# v3.net
KiCad netlist of a schematic drawn in EAGLE
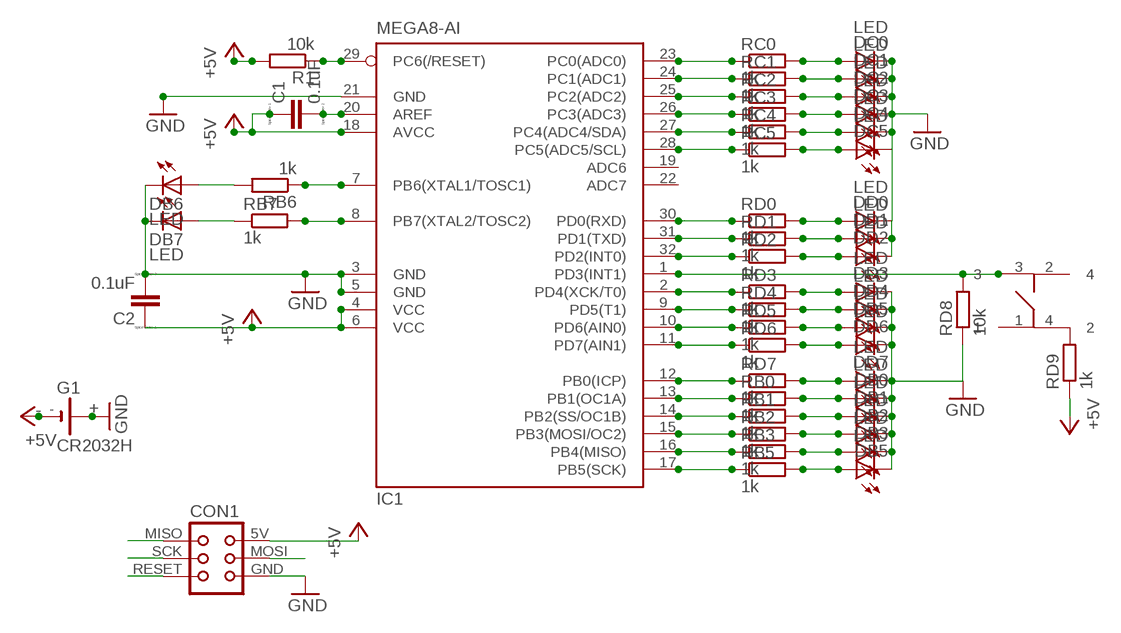
[diagram p0: schematic, sheet 1]

(export (version "E")
  (design (tool "Eeschema 10.0.6"))
  (components
    (comp (ref "C1")
      (value "0.1uF")
      (footprint "eagle-import:C0402")
      (libsource (lib "eagle-import") (part "CC0402"))
    )
    (comp (ref "C2")
      (value "0.1uF")
      (footprint "eagle-import:C0402")
      (libsource (lib "eagle-import") (part "CC0402"))
    )
    (comp (ref "CON1")
      (value "TINYISPT")
      (footprint "eagle-import:TC2030-MCP-NL")
      (libsource (lib "eagle-import") (part "TINYISPT"))
    )
    (comp (ref "DB0")
      (value "LED")
      (footprint "eagle-import:D0402")
      (libsource (lib "eagle-import") (part "LED"))
    )
    (comp (ref "DB1")
      (value "LED")
      (footprint "eagle-import:D0402")
      (libsource (lib "eagle-import") (part "LED"))
    )
    (comp (ref "DB2")
      (value "LED")
      (footprint "eagle-import:D0402")
      (libsource (lib "eagle-import") (part "LED"))
    )
    (comp (ref "DB3")
      (value "LED")
      (footprint "eagle-import:D0402")
      (libsource (lib "eagle-import") (part "LED"))
    )
    (comp (ref "DB5")
      (value "LED")
      (footprint "eagle-import:D0402")
      (libsource (lib "eagle-import") (part "LED"))
    )
    (comp (ref "DB6")
      (value "LED")
      (footprint "eagle-import:D0402")
      (libsource (lib "eagle-import") (part "LED"))
    )
    (comp (ref "DB7")
      (value "LED")
      (footprint "eagle-import:D0402")
      (libsource (lib "eagle-import") (part "LED"))
    )
    (comp (ref "DC0")
      (value "LED")
      (footprint "eagle-import:D0402")
      (libsource (lib "eagle-import") (part "LED"))
    )
    (comp (ref "DC1")
      (value "LED")
      (footprint "eagle-import:D0402")
      (libsource (lib "eagle-import") (part "LED"))
    )
    (comp (ref "DC2")
      (value "LED")
      (footprint "eagle-import:D0402")
      (libsource (lib "eagle-import") (part "LED"))
    )
    (comp (ref "DC3")
      (value "LED")
      (footprint "eagle-import:D0402")
      (libsource (lib "eagle-import") (part "LED"))
    )
    (comp (ref "DC4")
      (value "LED")
      (footprint "eagle-import:D0402")
      (libsource (lib "eagle-import") (part "LED"))
    )
    (comp (ref "DC5")
      (value "LED")
      (footprint "eagle-import:D0402")
      (libsource (lib "eagle-import") (part "LED"))
    )
    (comp (ref "DD0")
      (value "LED")
      (footprint "eagle-import:D0402")
      (libsource (lib "eagle-import") (part "LED"))
    )
    (comp (ref "DD1")
      (value "LED")
      (footprint "eagle-import:D0402")
      (libsource (lib "eagle-import") (part "LED"))
    )
    (comp (ref "DD2")
      (value "LED")
      (footprint "eagle-import:D0402")
      (libsource (lib "eagle-import") (part "LED"))
    )
    (comp (ref "DD3")
      (value "LED")
      (footprint "eagle-import:D0402")
      (libsource (lib "eagle-import") (part "LED"))
    )
    (comp (ref "DD4")
      (value "LED")
      (footprint "eagle-import:D0402")
      (libsource (lib "eagle-import") (part "LED"))
    )
    (comp (ref "DD5")
      (value "LED")
      (footprint "eagle-import:D0402")
      (libsource (lib "eagle-import") (part "LED"))
    )
    (comp (ref "DD6")
      (value "LED")
      (footprint "eagle-import:D0402")
      (libsource (lib "eagle-import") (part "LED"))
    )
    (comp (ref "DD7")
      (value "LED")
      (footprint "eagle-import:D0402")
      (libsource (lib "eagle-import") (part "LED"))
    )
    (comp (ref "G1")
      (value "CR2032H")
      (footprint "eagle-import:CR2032H")
      (libsource (lib "eagle-import") (part "CR2032H"))
    )
    (comp (ref "IC1")
      (value "MEGA8-AI")
      (footprint "eagle-import:TQFP32-08")
      (fields (field (name "MPN") "ATMEGA8-16AU"))
      (libsource (lib "eagle-import") (part "MEGA8-AI"))
    )
    (comp (ref "R1")
      (value "10k")
      (footprint "eagle-import:R0402")
      (libsource (lib "eagle-import") (part "R-EU_R0402"))
    )
    (comp (ref "RB0")
      (value "1k")
      (footprint "eagle-import:R0402")
      (libsource (lib "eagle-import") (part "R-EU_R0402"))
    )
    (comp (ref "RB1")
      (value "1k")
      (footprint "eagle-import:R0402")
      (libsource (lib "eagle-import") (part "R-EU_R0402"))
    )
    (comp (ref "RB2")
      (value "1k")
      (footprint "eagle-import:R0402")
      (libsource (lib "eagle-import") (part "R-EU_R0402"))
    )
    (comp (ref "RB3")
      (value "1k")
      (footprint "eagle-import:R0402")
      (libsource (lib "eagle-import") (part "R-EU_R0402"))
    )
    (comp (ref "RB5")
      (value "1k")
      (footprint "eagle-import:R0402")
      (libsource (lib "eagle-import") (part "R-EU_R0402"))
    )
    (comp (ref "RB6")
      (value "1k")
      (footprint "eagle-import:R0402")
      (libsource (lib "eagle-import") (part "R-EU_R0402"))
    )
    (comp (ref "RB7")
      (value "1k")
      (footprint "eagle-import:R0402")
      (libsource (lib "eagle-import") (part "R-EU_R0402"))
    )
    (comp (ref "RC0")
      (value "1k")
      (footprint "eagle-import:R0402")
      (libsource (lib "eagle-import") (part "R-EU_R0402"))
    )
    (comp (ref "RC1")
      (value "1k")
      (footprint "eagle-import:R0402")
      (libsource (lib "eagle-import") (part "R-EU_R0402"))
    )
    (comp (ref "RC2")
      (value "1k")
      (footprint "eagle-import:R0402")
      (libsource (lib "eagle-import") (part "R-EU_R0402"))
    )
    (comp (ref "RC3")
      (value "1k")
      (footprint "eagle-import:R0402")
      (libsource (lib "eagle-import") (part "R-EU_R0402"))
    )
    (comp (ref "RC4")
      (value "1k")
      (footprint "eagle-import:R0402")
      (libsource (lib "eagle-import") (part "R-EU_R0402"))
    )
    (comp (ref "RC5")
      (value "1k")
      (footprint "eagle-import:R0402")
      (libsource (lib "eagle-import") (part "R-EU_R0402"))
    )
    (comp (ref "RD0")
      (value "1k")
      (footprint "eagle-import:R0402")
      (libsource (lib "eagle-import") (part "R-EU_R0402"))
    )
    (comp (ref "RD1")
      (value "1k")
      (footprint "eagle-import:R0402")
      (libsource (lib "eagle-import") (part "R-EU_R0402"))
    )
    (comp (ref "RD2")
      (value "1k")
      (footprint "eagle-import:R0402")
      (libsource (lib "eagle-import") (part "R-EU_R0402"))
    )
    (comp (ref "RD3")
      (value "1k")
      (footprint "eagle-import:R0402")
      (libsource (lib "eagle-import") (part "R-EU_R0402"))
    )
    (comp (ref "RD4")
      (value "1k")
      (footprint "eagle-import:R0402")
      (libsource (lib "eagle-import") (part "R-EU_R0402"))
    )
    (comp (ref "RD5")
      (value "1k")
      (footprint "eagle-import:R0402")
      (libsource (lib "eagle-import") (part "R-EU_R0402"))
    )
    (comp (ref "RD6")
      (value "1k")
      (footprint "eagle-import:R0402")
      (libsource (lib "eagle-import") (part "R-EU_R0402"))
    )
    (comp (ref "RD7")
      (value "1k")
      (footprint "eagle-import:R0402")
      (libsource (lib "eagle-import") (part "R-EU_R0402"))
    )
    (comp (ref "RD8")
      (value "10k")
      (footprint "eagle-import:R0402")
      (libsource (lib "eagle-import") (part "R-EU_R0402"))
    )
    (comp (ref "RD9")
      (value "1k")
      (footprint "eagle-import:R0402")
      (libsource (lib "eagle-import") (part "R-EU_R0402"))
    )
    (comp (ref "U$2")
      (value "TEUCH4MM")
      (footprint "eagle-import:TEUCH4MM")
      (libsource (lib "eagle-import") (part "TEUCH4MM"))
    )
  )
  (nets
    (net (code "1") (name "+5V") (class "Default")
      (node (ref "C1") (pin "1") (pinfunction "1_1") (pintype "passive"))
      (node (ref "C2") (pin "1") (pinfunction "1_1") (pintype "passive"))
      (node (ref "CON1") (pin "5V") (pinfunction "VCC_5V") (pintype "passive"))
      (node (ref "G1") (pin "-") (pinfunction "-_-") (pintype "passive"))
      (node (ref "IC1") (pin "18") (pinfunction "AVCC_18") (pintype "power_in"))
      (node (ref "IC1") (pin "4") (pinfunction "VCC_4") (pintype "power_in"))
      (node (ref "IC1") (pin "6") (pinfunction "VCC_6") (pintype "power_in"))
      (node (ref "R1") (pin "2") (pinfunction "2_2") (pintype "passive"))
      (node (ref "RD9") (pin "1") (pinfunction "1_1") (pintype "passive"))
    )
    (net (code "2") (name "/RESET") (class "Default")
      (node (ref "CON1") (pin "RESET") (pinfunction "RESET_RESET") (pintype "passive"))
      (node (ref "IC1") (pin "29") (pinfunction "PC6(/RESET)_29") (pintype "bidirectional"))
      (node (ref "R1") (pin "1") (pinfunction "1_1") (pintype "passive"))
    )
    (net (code "3") (name "GND") (class "Default")
      (node (ref "C2") (pin "2") (pinfunction "2_2") (pintype "passive"))
      (node (ref "CON1") (pin "GND") (pinfunction "GND_GND") (pintype "passive"))
      (node (ref "DB0") (pin "C") (pinfunction "C_C") (pintype "passive"))
      (node (ref "DB1") (pin "C") (pinfunction "C_C") (pintype "passive"))
      (node (ref "DB2") (pin "C") (pinfunction "C_C") (pintype "passive"))
      (node (ref "DB3") (pin "C") (pinfunction "C_C") (pintype "passive"))
      (node (ref "DB5") (pin "C") (pinfunction "C_C") (pintype "passive"))
      (node (ref "DB6") (pin "C") (pinfunction "C_C") (pintype "passive"))
      (node (ref "DB7") (pin "C") (pinfunction "C_C") (pintype "passive"))
      (node (ref "DC0") (pin "C") (pinfunction "C_C") (pintype "passive"))
      (node (ref "DC1") (pin "C") (pinfunction "C_C") (pintype "passive"))
      (node (ref "DC2") (pin "C") (pinfunction "C_C") (pintype "passive"))
      (node (ref "DC3") (pin "C") (pinfunction "C_C") (pintype "passive"))
      (node (ref "DC4") (pin "C") (pinfunction "C_C") (pintype "passive"))
      (node (ref "DC5") (pin "C") (pinfunction "C_C") (pintype "passive"))
      (node (ref "DD0") (pin "C") (pinfunction "C_C") (pintype "passive"))
      (node (ref "DD1") (pin "C") (pinfunction "C_C") (pintype "passive"))
      (node (ref "DD2") (pin "C") (pinfunction "C_C") (pintype "passive"))
      (node (ref "DD3") (pin "C") (pinfunction "C_C") (pintype "passive"))
      (node (ref "DD4") (pin "C") (pinfunction "C_C") (pintype "passive"))
      (node (ref "DD5") (pin "C") (pinfunction "C_C") (pintype "passive"))
      (node (ref "DD6") (pin "C") (pinfunction "C_C") (pintype "passive"))
      (node (ref "DD7") (pin "C") (pinfunction "C_C") (pintype "passive"))
      (node (ref "G1") (pin "+") (pinfunction "+_+") (pintype "passive"))
      (node (ref "IC1") (pin "21") (pinfunction "GND_21") (pintype "power_in"))
      (node (ref "IC1") (pin "3") (pinfunction "GND_3") (pintype "power_in"))
      (node (ref "IC1") (pin "5") (pinfunction "GND_5") (pintype "power_in"))
      (node (ref "RD8") (pin "1") (pinfunction "1_1") (pintype "passive"))
    )
    (net (code "4") (name "Net-(DB0-PadA)") (class "Default")
      (node (ref "DB0") (pin "A") (pinfunction "A_A") (pintype "passive"))
      (node (ref "RB0") (pin "2") (pinfunction "2_2") (pintype "passive"))
    )
    (net (code "5") (name "Net-(DB1-PadA)") (class "Default")
      (node (ref "DB1") (pin "A") (pinfunction "A_A") (pintype "passive"))
      (node (ref "RB1") (pin "2") (pinfunction "2_2") (pintype "passive"))
    )
    (net (code "6") (name "Net-(DB2-PadA)") (class "Default")
      (node (ref "DB2") (pin "A") (pinfunction "A_A") (pintype "passive"))
      (node (ref "RB2") (pin "2") (pinfunction "2_2") (pintype "passive"))
    )
    (net (code "7") (name "Net-(DB3-PadA)") (class "Default")
      (node (ref "DB3") (pin "A") (pinfunction "A_A") (pintype "passive"))
      (node (ref "RB3") (pin "2") (pinfunction "2_2") (pintype "passive"))
    )
    (net (code "8") (name "Net-(DB5-PadA)") (class "Default")
      (node (ref "DB5") (pin "A") (pinfunction "A_A") (pintype "passive"))
      (node (ref "RB5") (pin "2") (pinfunction "2_2") (pintype "passive"))
    )
    (net (code "9") (name "Net-(DB6-PadA)") (class "Default")
      (node (ref "DB6") (pin "A") (pinfunction "A_A") (pintype "passive"))
      (node (ref "RB6") (pin "2") (pinfunction "2_2") (pintype "passive"))
    )
    (net (code "10") (name "Net-(DB7-PadA)") (class "Default")
      (node (ref "DB7") (pin "A") (pinfunction "A_A") (pintype "passive"))
      (node (ref "RB7") (pin "1") (pinfunction "1_1") (pintype "passive"))
    )
    (net (code "11") (name "Net-(DC0-PadA)") (class "Default")
      (node (ref "DC0") (pin "A") (pinfunction "A_A") (pintype "passive"))
      (node (ref "RC0") (pin "2") (pinfunction "2_2") (pintype "passive"))
    )
    (net (code "12") (name "Net-(DC1-PadA)") (class "Default")
      (node (ref "DC1") (pin "A") (pinfunction "A_A") (pintype "passive"))
      (node (ref "RC1") (pin "2") (pinfunction "2_2") (pintype "passive"))
    )
    (net (code "13") (name "Net-(DC2-PadA)") (class "Default")
      (node (ref "DC2") (pin "A") (pinfunction "A_A") (pintype "passive"))
      (node (ref "RC2") (pin "2") (pinfunction "2_2") (pintype "passive"))
    )
    (net (code "14") (name "Net-(DC3-PadA)") (class "Default")
      (node (ref "DC3") (pin "A") (pinfunction "A_A") (pintype "passive"))
      (node (ref "RC3") (pin "2") (pinfunction "2_2") (pintype "passive"))
    )
    (net (code "15") (name "Net-(DC4-PadA)") (class "Default")
      (node (ref "DC4") (pin "A") (pinfunction "A_A") (pintype "passive"))
      (node (ref "RC4") (pin "2") (pinfunction "2_2") (pintype "passive"))
    )
    (net (code "16") (name "Net-(DC5-PadA)") (class "Default")
      (node (ref "DC5") (pin "A") (pinfunction "A_A") (pintype "passive"))
      (node (ref "RC5") (pin "2") (pinfunction "2_2") (pintype "passive"))
    )
    (net (code "17") (name "Net-(DD0-PadA)") (class "Default")
      (node (ref "DD0") (pin "A") (pinfunction "A_A") (pintype "passive"))
      (node (ref "RD0") (pin "2") (pinfunction "2_2") (pintype "passive"))
    )
    (net (code "18") (name "Net-(DD1-PadA)") (class "Default")
      (node (ref "DD1") (pin "A") (pinfunction "A_A") (pintype "passive"))
      (node (ref "RD1") (pin "2") (pinfunction "2_2") (pintype "passive"))
    )
    (net (code "19") (name "Net-(DD2-PadA)") (class "Default")
      (node (ref "DD2") (pin "A") (pinfunction "A_A") (pintype "passive"))
      (node (ref "RD2") (pin "2") (pinfunction "2_2") (pintype "passive"))
    )
    (net (code "20") (name "Net-(DD3-PadA)") (class "Default")
      (node (ref "DD3") (pin "A") (pinfunction "A_A") (pintype "passive"))
      (node (ref "RD3") (pin "2") (pinfunction "2_2") (pintype "passive"))
    )
    (net (code "21") (name "Net-(DD4-PadA)") (class "Default")
      (node (ref "DD4") (pin "A") (pinfunction "A_A") (pintype "passive"))
      (node (ref "RD4") (pin "2") (pinfunction "2_2") (pintype "passive"))
    )
    (net (code "22") (name "Net-(DD5-PadA)") (class "Default")
      (node (ref "DD5") (pin "A") (pinfunction "A_A") (pintype "passive"))
      (node (ref "RD5") (pin "2") (pinfunction "2_2") (pintype "passive"))
    )
    (net (code "23") (name "Net-(DD6-PadA)") (class "Default")
      (node (ref "DD6") (pin "A") (pinfunction "A_A") (pintype "passive"))
      (node (ref "RD6") (pin "2") (pinfunction "2_2") (pintype "passive"))
    )
    (net (code "24") (name "Net-(DD7-PadA)") (class "Default")
      (node (ref "DD7") (pin "A") (pinfunction "A_A") (pintype "passive"))
      (node (ref "RD7") (pin "2") (pinfunction "2_2") (pintype "passive"))
    )
    (net (code "25") (name "Net-(IC1-AREF)") (class "Default")
      (node (ref "C1") (pin "2") (pinfunction "2_2") (pintype "passive"))
      (node (ref "IC1") (pin "20") (pinfunction "AREF_20") (pintype "passive"))
    )
    (net (code "26") (name "Net-(IC1-PB0(ICP))") (class "Default")
      (node (ref "IC1") (pin "12") (pinfunction "PB0(ICP)_12") (pintype "bidirectional"))
      (node (ref "RD7") (pin "1") (pinfunction "1_1") (pintype "passive"))
    )
    (net (code "27") (name "Net-(IC1-PB1(OC1A))") (class "Default")
      (node (ref "IC1") (pin "13") (pinfunction "PB1(OC1A)_13") (pintype "bidirectional"))
      (node (ref "RB0") (pin "1") (pinfunction "1_1") (pintype "passive"))
    )
    (net (code "28") (name "Net-(IC1-PB2(SS{slash}OC1B))") (class "Default")
      (node (ref "IC1") (pin "14") (pinfunction "PB2(SS/OC1B)_14") (pintype "bidirectional"))
      (node (ref "RB1") (pin "1") (pinfunction "1_1") (pintype "passive"))
    )
    (net (code "29") (name "Net-(IC1-PB3(MOSI{slash}OC2))") (class "Default")
      (node (ref "IC1") (pin "15") (pinfunction "PB3(MOSI/OC2)_15") (pintype "bidirectional"))
      (node (ref "RB2") (pin "1") (pinfunction "1_1") (pintype "passive"))
    )
    (net (code "30") (name "Net-(IC1-PB4(MISO))") (class "Default")
      (node (ref "IC1") (pin "16") (pinfunction "PB4(MISO)_16") (pintype "bidirectional"))
      (node (ref "RB3") (pin "1") (pinfunction "1_1") (pintype "passive"))
    )
    (net (code "31") (name "Net-(IC1-PB5(SCK))") (class "Default")
      (node (ref "IC1") (pin "17") (pinfunction "PB5(SCK)_17") (pintype "bidirectional"))
      (node (ref "RB5") (pin "1") (pinfunction "1_1") (pintype "passive"))
    )
    (net (code "32") (name "Net-(IC1-PB6(XTAL1{slash}TOSC1))") (class "Default")
      (node (ref "IC1") (pin "7") (pinfunction "PB6(XTAL1/TOSC1)_7") (pintype "bidirectional"))
      (node (ref "RB6") (pin "1") (pinfunction "1_1") (pintype "passive"))
    )
    (net (code "33") (name "Net-(IC1-PB7(XTAL2{slash}TOSC2))") (class "Default")
      (node (ref "IC1") (pin "8") (pinfunction "PB7(XTAL2/TOSC2)_8") (pintype "bidirectional"))
      (node (ref "RB7") (pin "2") (pinfunction "2_2") (pintype "passive"))
    )
    (net (code "34") (name "Net-(IC1-PC0(ADC0))") (class "Default")
      (node (ref "IC1") (pin "23") (pinfunction "PC0(ADC0)_23") (pintype "bidirectional"))
      (node (ref "RC0") (pin "1") (pinfunction "1_1") (pintype "passive"))
    )
    (net (code "35") (name "Net-(IC1-PC1(ADC1))") (class "Default")
      (node (ref "IC1") (pin "24") (pinfunction "PC1(ADC1)_24") (pintype "bidirectional"))
      (node (ref "RC1") (pin "1") (pinfunction "1_1") (pintype "passive"))
    )
    (net (code "36") (name "Net-(IC1-PC2(ADC2))") (class "Default")
      (node (ref "IC1") (pin "25") (pinfunction "PC2(ADC2)_25") (pintype "bidirectional"))
      (node (ref "RC2") (pin "1") (pinfunction "1_1") (pintype "passive"))
    )
    (net (code "37") (name "Net-(IC1-PC3(ADC3))") (class "Default")
      (node (ref "IC1") (pin "26") (pinfunction "PC3(ADC3)_26") (pintype "bidirectional"))
      (node (ref "RC3") (pin "1") (pinfunction "1_1") (pintype "passive"))
    )
    (net (code "38") (name "Net-(IC1-PC4(ADC4{slash}SDA))") (class "Default")
      (node (ref "IC1") (pin "27") (pinfunction "PC4(ADC4/SDA)_27") (pintype "bidirectional"))
      (node (ref "RC4") (pin "1") (pinfunction "1_1") (pintype "passive"))
    )
    (net (code "39") (name "Net-(IC1-PC5(ADC5{slash}SCL))") (class "Default")
      (node (ref "IC1") (pin "28") (pinfunction "PC5(ADC5/SCL)_28") (pintype "bidirectional"))
      (node (ref "RC5") (pin "1") (pinfunction "1_1") (pintype "passive"))
    )
    (net (code "40") (name "Net-(IC1-PD0(RXD))") (class "Default")
      (node (ref "IC1") (pin "30") (pinfunction "PD0(RXD)_30") (pintype "bidirectional"))
      (node (ref "RD0") (pin "1") (pinfunction "1_1") (pintype "passive"))
    )
    (net (code "41") (name "Net-(IC1-PD1(TXD))") (class "Default")
      (node (ref "IC1") (pin "31") (pinfunction "PD1(TXD)_31") (pintype "bidirectional"))
      (node (ref "RD1") (pin "1") (pinfunction "1_1") (pintype "passive"))
    )
    (net (code "42") (name "Net-(IC1-PD2(INT0))") (class "Default")
      (node (ref "IC1") (pin "32") (pinfunction "PD2(INT0)_32") (pintype "bidirectional"))
      (node (ref "RD2") (pin "1") (pinfunction "1_1") (pintype "passive"))
    )
    (net (code "43") (name "Net-(IC1-PD3(INT1))") (class "Default")
      (node (ref "IC1") (pin "1") (pinfunction "PD3(INT1)_1") (pintype "bidirectional"))
      (node (ref "RD8") (pin "2") (pinfunction "2_2") (pintype "passive"))
    )
    (net (code "44") (name "Net-(IC1-PD4(XCK{slash}T0))") (class "Default")
      (node (ref "IC1") (pin "2") (pinfunction "PD4(XCK/T0)_2") (pintype "bidirectional"))
      (node (ref "RD3") (pin "1") (pinfunction "1_1") (pintype "passive"))
    )
    (net (code "45") (name "Net-(IC1-PD5(T1))") (class "Default")
      (node (ref "IC1") (pin "9") (pinfunction "PD5(T1)_9") (pintype "bidirectional"))
      (node (ref "RD4") (pin "1") (pinfunction "1_1") (pintype "passive"))
    )
    (net (code "46") (name "Net-(IC1-PD6(AIN0))") (class "Default")
      (node (ref "IC1") (pin "10") (pinfunction "PD6(AIN0)_10") (pintype "bidirectional"))
      (node (ref "RD5") (pin "1") (pinfunction "1_1") (pintype "passive"))
    )
    (net (code "47") (name "Net-(IC1-PD7(AIN1))") (class "Default")
      (node (ref "IC1") (pin "11") (pinfunction "PD7(AIN1)_11") (pintype "bidirectional"))
      (node (ref "RD6") (pin "1") (pinfunction "1_1") (pintype "passive"))
    )
    (net (code "48") (name "Net-(U$2-2)") (class "Default")
      (node (ref "U$2") (pin "1") (pinfunction "1_1") (pintype "bidirectional"))
      (node (ref "U$2") (pin "4") (pinfunction "2_4") (pintype "bidirectional"))
    )
    (net (code "49") (name "Net-(U$2-4)") (class "Default")
      (node (ref "U$2") (pin "2") (pinfunction "4_2") (pintype "bidirectional"))
      (node (ref "U$2") (pin "3") (pinfunction "3_3") (pintype "bidirectional"))
    )
    (net (code "50") (name "unconnected-(CON1-PadMISO)") (class "Default")
      (node (ref "CON1") (pin "MISO") (pinfunction "MISO_MISO") (pintype "passive"))
    )
    (net (code "51") (name "unconnected-(CON1-PadMOSI)") (class "Default")
      (node (ref "CON1") (pin "MOSI") (pinfunction "MOSI_MOSI") (pintype "passive"))
    )
    (net (code "52") (name "unconnected-(CON1-PadSCK)") (class "Default")
      (node (ref "CON1") (pin "SCK") (pinfunction "SCK_SCK") (pintype "passive"))
    )
    (net (code "53") (name "unconnected-(IC1-ADC6-Pad19)") (class "Default")
      (node (ref "IC1") (pin "19") (pinfunction "ADC6_19") (pintype "bidirectional"))
    )
    (net (code "54") (name "unconnected-(IC1-ADC7-Pad22)") (class "Default")
      (node (ref "IC1") (pin "22") (pinfunction "ADC7_22") (pintype "bidirectional"))
    )
    (net (code "55") (name "unconnected-(RD9-Pad2)") (class "Default")
      (node (ref "RD9") (pin "2") (pinfunction "2_2") (pintype "passive"))
    )
  )
)
